# Blinky_Board.net
KiCad netlist of a schematic drawn in EAGLE
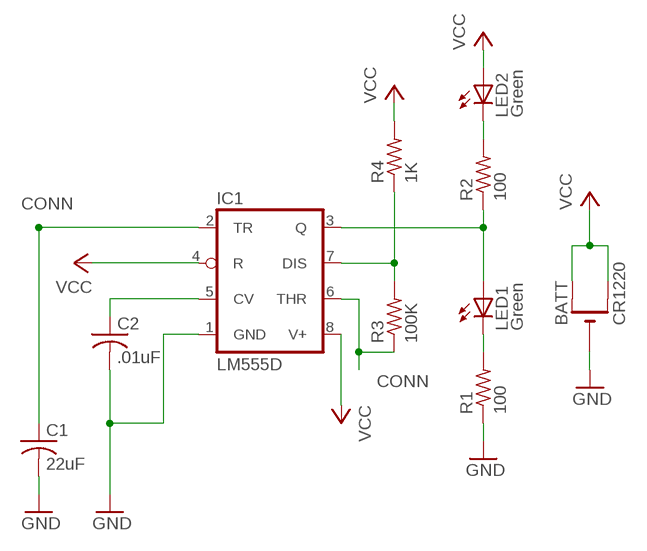
[diagram p0: schematic, sheet 1]

(export (version "E")
  (design (tool "Eeschema 10.0.6"))
  (components
    (comp (ref "BATT")
      (value "CR1220")
      (footprint "eagle-import:CR1220-SMD")
      (libsource (lib "eagle-import") (part "CR1220SMT"))
    )
    (comp (ref "C1")
      (value "22uF")
      (footprint "eagle-import:C0805")
      (fields (field (name "MPN") "C2012X5R1A226K125AB"))
      (libsource (lib "eagle-import") (part "C-USC0805"))
    )
    (comp (ref "C2")
      (value ".01uF")
      (footprint "eagle-import:C0805")
      (fields (field (name "MPN") "GRM216R71H103KA01D"))
      (libsource (lib "eagle-import") (part "C-USC0805"))
    )
    (comp (ref "IC1")
      (value "LM555D")
      (footprint "eagle-import:SO08")
      (fields (field (name "MPN") "TLC555CD."))
      (libsource (lib "eagle-import") (part "555DLM"))
    )
    (comp (ref "LED1")
      (value "Green")
      (footprint "eagle-import:CHIPLED_0805")
      (fields (field (name "MPN") "150080GS75000"))
      (libsource (lib "eagle-import") (part "LEDCHIPLED_0805"))
    )
    (comp (ref "LED2")
      (value "Green")
      (footprint "eagle-import:CHIPLED_0805")
      (fields (field (name "MPN") "150080GS75000"))
      (libsource (lib "eagle-import") (part "LEDCHIPLED_0805"))
    )
    (comp (ref "R1")
      (value "100")
      (footprint "eagle-import:R0805")
      (fields (field (name "MPN") "CR0805-FX-1000-ELF"))
      (libsource (lib "eagle-import") (part "R-US_R0805"))
    )
    (comp (ref "R2")
      (value "100")
      (footprint "eagle-import:R0805")
      (fields (field (name "MPN") "CR0805-FX-1000-ELF"))
      (libsource (lib "eagle-import") (part "R-US_R0805"))
    )
    (comp (ref "R3")
      (value "100K")
      (footprint "eagle-import:R0805")
      (fields (field (name "MPN") "MCHV05WAJ0104T5E"))
      (libsource (lib "eagle-import") (part "R-US_R0805"))
    )
    (comp (ref "R4")
      (value "1K")
      (footprint "eagle-import:R0805")
      (fields (field (name "MF") "VISHAY/DALE") (field (name "MPN") "CRCW08051K00FKTA"))
      (libsource (lib "eagle-import") (part "R-US_R0805"))
    )
  )
  (nets
    (net (code "1") (name "/CONN") (class "Default")
      (node (ref "C1") (pin "1") (pinfunction "1_1") (pintype "passive"))
      (node (ref "IC1") (pin "2") (pinfunction "TR_2") (pintype "input"))
      (node (ref "IC1") (pin "6") (pinfunction "THR_6") (pintype "input"))
      (node (ref "R3") (pin "1") (pinfunction "1_1") (pintype "passive"))
    )
    (net (code "2") (name "GND") (class "Default")
      (node (ref "BATT") (pin "-") (pinfunction "-_-") (pintype "passive"))
      (node (ref "C1") (pin "2") (pinfunction "2_2") (pintype "passive"))
      (node (ref "C2") (pin "2") (pinfunction "2_2") (pintype "passive"))
      (node (ref "IC1") (pin "1") (pinfunction "GND_1") (pintype "power_in"))
      (node (ref "R1") (pin "1") (pinfunction "1_1") (pintype "passive"))
    )
    (net (code "3") (name "Net-(IC1-CV)") (class "Default")
      (node (ref "C2") (pin "1") (pinfunction "1_1") (pintype "passive"))
      (node (ref "IC1") (pin "5") (pinfunction "CV_5") (pintype "input"))
    )
    (net (code "4") (name "Net-(IC1-DIS)") (class "Default")
      (node (ref "IC1") (pin "7") (pinfunction "DIS_7") (pintype "input"))
      (node (ref "R3") (pin "2") (pinfunction "2_2") (pintype "passive"))
      (node (ref "R4") (pin "1") (pinfunction "1_1") (pintype "passive"))
    )
    (net (code "5") (name "Net-(IC1-Q)") (class "Default")
      (node (ref "IC1") (pin "3") (pinfunction "Q_3") (pintype "output"))
      (node (ref "LED1") (pin "A") (pinfunction "A_A") (pintype "passive"))
      (node (ref "R2") (pin "1") (pinfunction "1_1") (pintype "passive"))
    )
    (net (code "6") (name "Net-(LED1-PadC)") (class "Default")
      (node (ref "LED1") (pin "C") (pinfunction "C_C") (pintype "passive"))
      (node (ref "R1") (pin "2") (pinfunction "2_2") (pintype "passive"))
    )
    (net (code "7") (name "Net-(LED2-PadC)") (class "Default")
      (node (ref "LED2") (pin "C") (pinfunction "C_C") (pintype "passive"))
      (node (ref "R2") (pin "2") (pinfunction "2_2") (pintype "passive"))
    )
    (net (code "8") (name "VCC") (class "Default")
      (node (ref "BATT") (pin "+$1") (pinfunction "+_+$1") (pintype "passive"))
      (node (ref "BATT") (pin "+$2") (pinfunction "+1_+$2") (pintype "passive"))
      (node (ref "IC1") (pin "4") (pinfunction "R_4") (pintype "input"))
      (node (ref "IC1") (pin "8") (pinfunction "V+_8") (pintype "power_in"))
      (node (ref "LED2") (pin "A") (pinfunction "A_A") (pintype "passive"))
      (node (ref "R4") (pin "2") (pinfunction "2_2") (pintype "passive"))
    )
  )
)
